# shield-v3.net
KiCad netlist of a schematic drawn in EAGLE
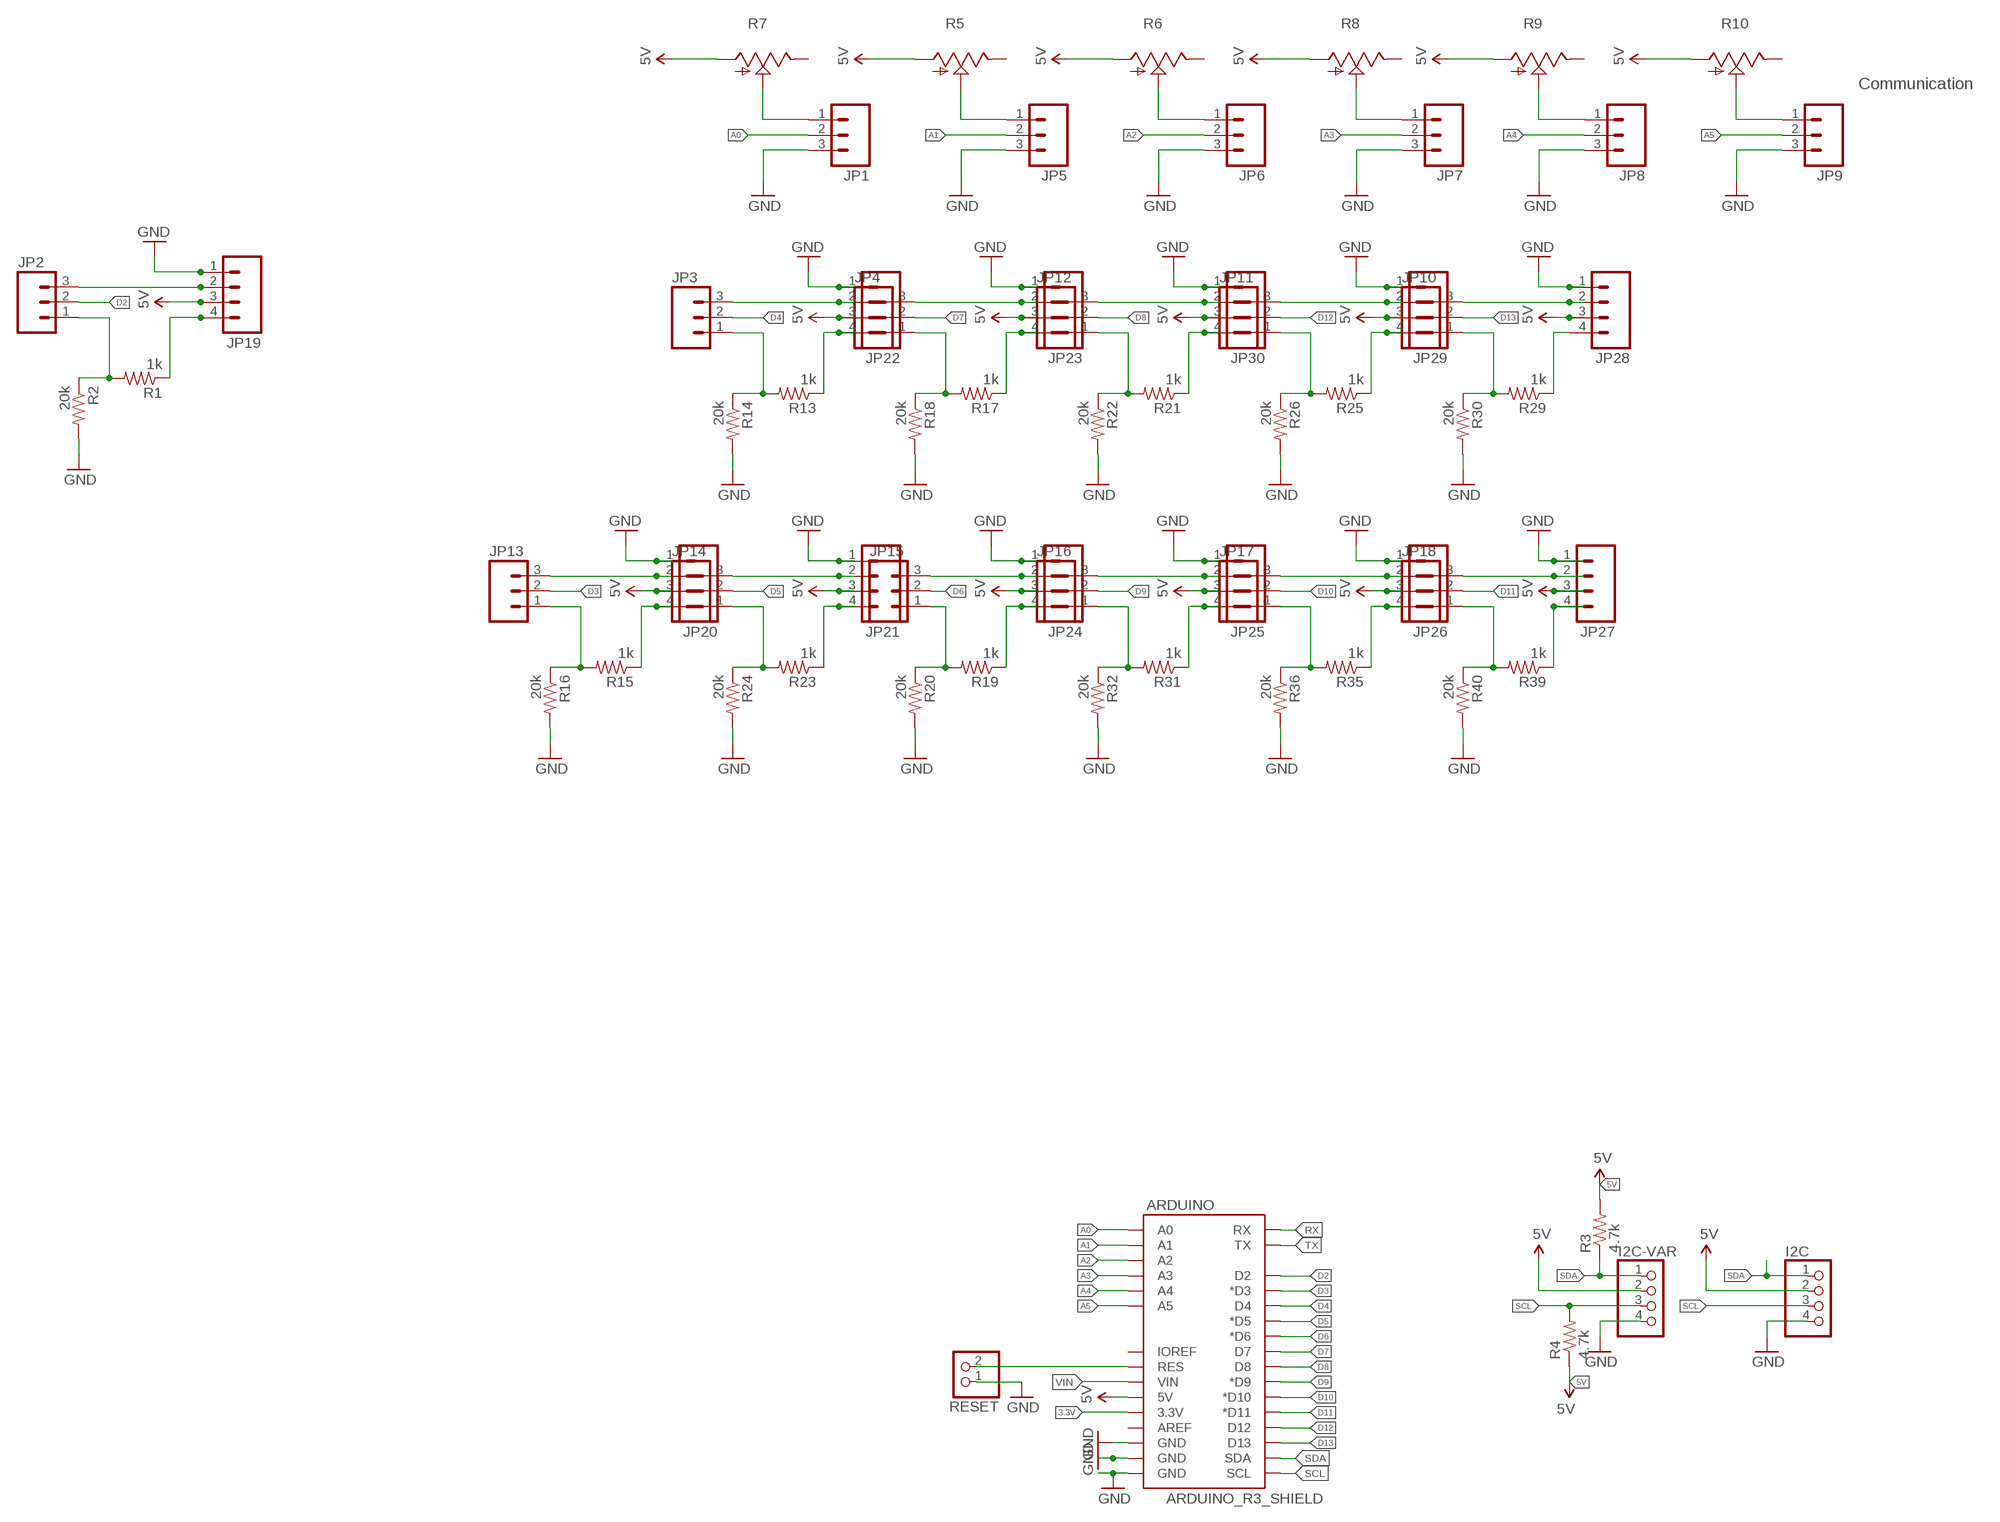
[diagram p0: schematic, sheet 1]

(export (version "E")
  (design (tool "Eeschema 10.0.6"))
  (components
    (comp (ref "ARDUINO")
      (value "ARDUINO_R3_SHIELD")
      (footprint "eagle-import:UNO_R3_SHIELD")
      (libsource (lib "eagle-import") (part "ARDUINO_R3_SHIELD"))
    )
    (comp (ref "I2C")
      (value "PINHD-1X4")
      (footprint "eagle-import:1X04")
      (libsource (lib "eagle-import") (part "PINHD-1X4"))
    )
    (comp (ref "I2C-VAR")
      (value "PINHD-1X4")
      (footprint "eagle-import:1X04")
      (libsource (lib "eagle-import") (part "PINHD-1X4"))
    )
    (comp (ref "JP1")
      (value "M03LOCK_NO_SILK")
      (footprint "eagle-import:1X03_LOCK_NO_SILK")
      (libsource (lib "eagle-import") (part "M03LOCK_NO_SILK"))
    )
    (comp (ref "JP2")
      (value "M03LOCK_NO_SILK")
      (footprint "eagle-import:1X03_LOCK_NO_SILK")
      (libsource (lib "eagle-import") (part "M03LOCK_NO_SILK"))
    )
    (comp (ref "JP3")
      (value "M03LOCK_NO_SILK")
      (footprint "eagle-import:1X03_LOCK_NO_SILK")
      (libsource (lib "eagle-import") (part "M03LOCK_NO_SILK"))
    )
    (comp (ref "JP4")
      (value "M03LOCK_NO_SILK")
      (footprint "eagle-import:1X03_LOCK_NO_SILK")
      (libsource (lib "eagle-import") (part "M03LOCK_NO_SILK"))
    )
    (comp (ref "JP5")
      (value "M03LOCK_NO_SILK")
      (footprint "eagle-import:1X03_LOCK_NO_SILK")
      (libsource (lib "eagle-import") (part "M03LOCK_NO_SILK"))
    )
    (comp (ref "JP6")
      (value "M03LOCK_NO_SILK")
      (footprint "eagle-import:1X03_LOCK_NO_SILK")
      (libsource (lib "eagle-import") (part "M03LOCK_NO_SILK"))
    )
    (comp (ref "JP7")
      (value "M03LOCK_NO_SILK")
      (footprint "eagle-import:1X03_LOCK_NO_SILK")
      (libsource (lib "eagle-import") (part "M03LOCK_NO_SILK"))
    )
    (comp (ref "JP8")
      (value "M03LOCK_NO_SILK")
      (footprint "eagle-import:1X03_LOCK_NO_SILK")
      (libsource (lib "eagle-import") (part "M03LOCK_NO_SILK"))
    )
    (comp (ref "JP9")
      (value "M03LOCK_NO_SILK")
      (footprint "eagle-import:1X03_LOCK_NO_SILK")
      (libsource (lib "eagle-import") (part "M03LOCK_NO_SILK"))
    )
    (comp (ref "JP10")
      (value "M03LOCK_NO_SILK")
      (footprint "eagle-import:1X03_LOCK_NO_SILK")
      (libsource (lib "eagle-import") (part "M03LOCK_NO_SILK"))
    )
    (comp (ref "JP11")
      (value "M03LOCK_NO_SILK")
      (footprint "eagle-import:1X03_LOCK_NO_SILK")
      (libsource (lib "eagle-import") (part "M03LOCK_NO_SILK"))
    )
    (comp (ref "JP12")
      (value "M03LOCK_NO_SILK")
      (footprint "eagle-import:1X03_LOCK_NO_SILK")
      (libsource (lib "eagle-import") (part "M03LOCK_NO_SILK"))
    )
    (comp (ref "JP13")
      (value "M03LOCK_NO_SILK")
      (footprint "eagle-import:1X03_LOCK_NO_SILK")
      (libsource (lib "eagle-import") (part "M03LOCK_NO_SILK"))
    )
    (comp (ref "JP14")
      (value "M03LOCK_NO_SILK")
      (footprint "eagle-import:1X03_LOCK_NO_SILK")
      (libsource (lib "eagle-import") (part "M03LOCK_NO_SILK"))
    )
    (comp (ref "JP15")
      (value "M03LOCK_NO_SILK")
      (footprint "eagle-import:1X03_LOCK_NO_SILK")
      (libsource (lib "eagle-import") (part "M03LOCK_NO_SILK"))
    )
    (comp (ref "JP16")
      (value "M03LOCK_NO_SILK")
      (footprint "eagle-import:1X03_LOCK_NO_SILK")
      (libsource (lib "eagle-import") (part "M03LOCK_NO_SILK"))
    )
    (comp (ref "JP17")
      (value "M03LOCK_NO_SILK")
      (footprint "eagle-import:1X03_LOCK_NO_SILK")
      (libsource (lib "eagle-import") (part "M03LOCK_NO_SILK"))
    )
    (comp (ref "JP18")
      (value "M03LOCK_NO_SILK")
      (footprint "eagle-import:1X03_LOCK_NO_SILK")
      (libsource (lib "eagle-import") (part "M03LOCK_NO_SILK"))
    )
    (comp (ref "JP19")
      (value "M04LOCK")
      (footprint "eagle-import:1X04_LOCK")
      (libsource (lib "eagle-import") (part "M04LOCK"))
    )
    (comp (ref "JP20")
      (value "M04LOCK")
      (footprint "eagle-import:1X04_LOCK")
      (libsource (lib "eagle-import") (part "M04LOCK"))
    )
    (comp (ref "JP21")
      (value "M04LOCK")
      (footprint "eagle-import:1X04_LOCK")
      (libsource (lib "eagle-import") (part "M04LOCK"))
    )
    (comp (ref "JP22")
      (value "M04LOCK")
      (footprint "eagle-import:1X04_LOCK")
      (libsource (lib "eagle-import") (part "M04LOCK"))
    )
    (comp (ref "JP23")
      (value "M04LOCK")
      (footprint "eagle-import:1X04_LOCK")
      (libsource (lib "eagle-import") (part "M04LOCK"))
    )
    (comp (ref "JP24")
      (value "M04LOCK")
      (footprint "eagle-import:1X04_LOCK")
      (libsource (lib "eagle-import") (part "M04LOCK"))
    )
    (comp (ref "JP25")
      (value "M04LOCK")
      (footprint "eagle-import:1X04_LOCK")
      (libsource (lib "eagle-import") (part "M04LOCK"))
    )
    (comp (ref "JP26")
      (value "M04LOCK")
      (footprint "eagle-import:1X04_LOCK")
      (libsource (lib "eagle-import") (part "M04LOCK"))
    )
    (comp (ref "JP27")
      (value "M04LOCK")
      (footprint "eagle-import:1X04_LOCK")
      (libsource (lib "eagle-import") (part "M04LOCK"))
    )
    (comp (ref "JP28")
      (value "M04LOCK")
      (footprint "eagle-import:1X04_LOCK")
      (libsource (lib "eagle-import") (part "M04LOCK"))
    )
    (comp (ref "JP29")
      (value "M04LOCK")
      (footprint "eagle-import:1X04_LOCK")
      (libsource (lib "eagle-import") (part "M04LOCK"))
    )
    (comp (ref "JP30")
      (value "M04LOCK")
      (footprint "eagle-import:1X04_LOCK")
      (libsource (lib "eagle-import") (part "M04LOCK"))
    )
    (comp (ref "R1")
      (value "1k")
      (footprint "eagle-import:AXIAL-0.3-KIT")
      (libsource (lib "eagle-import") (part "RESISTORKIT"))
    )
    (comp (ref "R2")
      (value "20k")
      (footprint "eagle-import:AXIAL-0.3-KIT")
      (libsource (lib "eagle-import") (part "RESISTORKIT"))
    )
    (comp (ref "R3")
      (value "4.7k")
      (footprint "eagle-import:AXIAL-0.3-KIT")
      (libsource (lib "eagle-import") (part "RESISTORKIT"))
    )
    (comp (ref "R4")
      (value "4.7k")
      (footprint "eagle-import:AXIAL-0.3-KIT")
      (libsource (lib "eagle-import") (part "RESISTORKIT"))
    )
    (comp (ref "R5")
      (value "TRIM_US-CA6V")
      (footprint "eagle-import:CA6V")
      (libsource (lib "eagle-import") (part "TRIM_US-CA6V"))
    )
    (comp (ref "R6")
      (value "TRIM_US-CA6V")
      (footprint "eagle-import:CA6V")
      (libsource (lib "eagle-import") (part "TRIM_US-CA6V"))
    )
    (comp (ref "R7")
      (value "TRIM_US-CA6V")
      (footprint "eagle-import:CA6V")
      (libsource (lib "eagle-import") (part "TRIM_US-CA6V"))
    )
    (comp (ref "R8")
      (value "TRIM_US-CA6V")
      (footprint "eagle-import:CA6V")
      (libsource (lib "eagle-import") (part "TRIM_US-CA6V"))
    )
    (comp (ref "R9")
      (value "TRIM_US-CA6V")
      (footprint "eagle-import:CA6V")
      (libsource (lib "eagle-import") (part "TRIM_US-CA6V"))
    )
    (comp (ref "R10")
      (value "TRIM_US-CA6V")
      (footprint "eagle-import:CA6V")
      (libsource (lib "eagle-import") (part "TRIM_US-CA6V"))
    )
    (comp (ref "R13")
      (value "1k")
      (footprint "eagle-import:AXIAL-0.3-KIT")
      (libsource (lib "eagle-import") (part "RESISTORKIT"))
    )
    (comp (ref "R14")
      (value "20k")
      (footprint "eagle-import:AXIAL-0.3-KIT")
      (libsource (lib "eagle-import") (part "RESISTORKIT"))
    )
    (comp (ref "R15")
      (value "1k")
      (footprint "eagle-import:AXIAL-0.3-KIT")
      (libsource (lib "eagle-import") (part "RESISTORKIT"))
    )
    (comp (ref "R16")
      (value "20k")
      (footprint "eagle-import:AXIAL-0.3-KIT")
      (libsource (lib "eagle-import") (part "RESISTORKIT"))
    )
    (comp (ref "R17")
      (value "1k")
      (footprint "eagle-import:AXIAL-0.3-KIT")
      (libsource (lib "eagle-import") (part "RESISTORKIT"))
    )
    (comp (ref "R18")
      (value "20k")
      (footprint "eagle-import:AXIAL-0.3-KIT")
      (libsource (lib "eagle-import") (part "RESISTORKIT"))
    )
    (comp (ref "R19")
      (value "1k")
      (footprint "eagle-import:AXIAL-0.3-KIT")
      (libsource (lib "eagle-import") (part "RESISTORKIT"))
    )
    (comp (ref "R20")
      (value "20k")
      (footprint "eagle-import:AXIAL-0.3-KIT")
      (libsource (lib "eagle-import") (part "RESISTORKIT"))
    )
    (comp (ref "R21")
      (value "1k")
      (footprint "eagle-import:AXIAL-0.3-KIT")
      (libsource (lib "eagle-import") (part "RESISTORKIT"))
    )
    (comp (ref "R22")
      (value "20k")
      (footprint "eagle-import:AXIAL-0.3-KIT")
      (libsource (lib "eagle-import") (part "RESISTORKIT"))
    )
    (comp (ref "R23")
      (value "1k")
      (footprint "eagle-import:AXIAL-0.3-KIT")
      (libsource (lib "eagle-import") (part "RESISTORKIT"))
    )
    (comp (ref "R24")
      (value "20k")
      (footprint "eagle-import:AXIAL-0.3-KIT")
      (libsource (lib "eagle-import") (part "RESISTORKIT"))
    )
    (comp (ref "R25")
      (value "1k")
      (footprint "eagle-import:AXIAL-0.3-KIT")
      (libsource (lib "eagle-import") (part "RESISTORKIT"))
    )
    (comp (ref "R26")
      (value "20k")
      (footprint "eagle-import:AXIAL-0.3-KIT")
      (libsource (lib "eagle-import") (part "RESISTORKIT"))
    )
    (comp (ref "R29")
      (value "1k")
      (footprint "eagle-import:AXIAL-0.3-KIT")
      (libsource (lib "eagle-import") (part "RESISTORKIT"))
    )
    (comp (ref "R30")
      (value "20k")
      (footprint "eagle-import:AXIAL-0.3-KIT")
      (libsource (lib "eagle-import") (part "RESISTORKIT"))
    )
    (comp (ref "R31")
      (value "1k")
      (footprint "eagle-import:AXIAL-0.3-KIT")
      (libsource (lib "eagle-import") (part "RESISTORKIT"))
    )
    (comp (ref "R32")
      (value "20k")
      (footprint "eagle-import:AXIAL-0.3-KIT")
      (libsource (lib "eagle-import") (part "RESISTORKIT"))
    )
    (comp (ref "R35")
      (value "1k")
      (footprint "eagle-import:AXIAL-0.3-KIT")
      (libsource (lib "eagle-import") (part "RESISTORKIT"))
    )
    (comp (ref "R36")
      (value "20k")
      (footprint "eagle-import:AXIAL-0.3-KIT")
      (libsource (lib "eagle-import") (part "RESISTORKIT"))
    )
    (comp (ref "R39")
      (value "1k")
      (footprint "eagle-import:AXIAL-0.3-KIT")
      (libsource (lib "eagle-import") (part "RESISTORKIT"))
    )
    (comp (ref "R40")
      (value "20k")
      (footprint "eagle-import:AXIAL-0.3-KIT")
      (libsource (lib "eagle-import") (part "RESISTORKIT"))
    )
    (comp (ref "RESET")
      (value "PINHD-1X2")
      (footprint "eagle-import:1X02")
      (libsource (lib "eagle-import") (part "PINHD-1X2"))
    )
  )
  (nets
    (net (code "1") (name "3.3V") (class "Default")
      (node (ref "ARDUINO") (pin "3.3V") (pinfunction "3.3V_3.3V") (pintype "bidirectional"))
    )
    (net (code "2") (name "5V") (class "Default")
      (node (ref "ARDUINO") (pin "5V") (pinfunction "5V_5V") (pintype "bidirectional"))
      (node (ref "I2C") (pin "2") (pinfunction "2_2") (pintype "passive"))
      (node (ref "I2C-VAR") (pin "2") (pinfunction "2_2") (pintype "passive"))
      (node (ref "JP19") (pin "3") (pinfunction "3_3") (pintype "passive"))
      (node (ref "JP20") (pin "3") (pinfunction "3_3") (pintype "passive"))
      (node (ref "JP21") (pin "3") (pinfunction "3_3") (pintype "passive"))
      (node (ref "JP22") (pin "3") (pinfunction "3_3") (pintype "passive"))
      (node (ref "JP23") (pin "3") (pinfunction "3_3") (pintype "passive"))
      (node (ref "JP24") (pin "3") (pinfunction "3_3") (pintype "passive"))
      (node (ref "JP25") (pin "3") (pinfunction "3_3") (pintype "passive"))
      (node (ref "JP26") (pin "3") (pinfunction "3_3") (pintype "passive"))
      (node (ref "JP27") (pin "3") (pinfunction "3_3") (pintype "passive"))
      (node (ref "JP28") (pin "3") (pinfunction "3_3") (pintype "passive"))
      (node (ref "JP29") (pin "3") (pinfunction "3_3") (pintype "passive"))
      (node (ref "JP30") (pin "3") (pinfunction "3_3") (pintype "passive"))
      (node (ref "R10") (pin "A") (pinfunction "A_A") (pintype "passive"))
      (node (ref "R3") (pin "P$2") (pinfunction "2_P$2") (pintype "passive"))
      (node (ref "R4") (pin "P$1") (pinfunction "1_P$1") (pintype "passive"))
      (node (ref "R5") (pin "A") (pinfunction "A_A") (pintype "passive"))
      (node (ref "R6") (pin "A") (pinfunction "A_A") (pintype "passive"))
      (node (ref "R7") (pin "A") (pinfunction "A_A") (pintype "passive"))
      (node (ref "R8") (pin "A") (pinfunction "A_A") (pintype "passive"))
      (node (ref "R9") (pin "A") (pinfunction "A_A") (pintype "passive"))
    )
    (net (code "3") (name "A0") (class "Default")
      (node (ref "ARDUINO") (pin "A0") (pinfunction "A0_A0") (pintype "bidirectional"))
      (node (ref "JP1") (pin "2") (pinfunction "2_2") (pintype "passive"))
    )
    (net (code "4") (name "A1") (class "Default")
      (node (ref "ARDUINO") (pin "A1") (pinfunction "A1_A1") (pintype "bidirectional"))
      (node (ref "JP5") (pin "2") (pinfunction "2_2") (pintype "passive"))
    )
    (net (code "5") (name "A2") (class "Default")
      (node (ref "ARDUINO") (pin "A2") (pinfunction "A2_A2") (pintype "bidirectional"))
      (node (ref "JP6") (pin "2") (pinfunction "2_2") (pintype "passive"))
    )
    (net (code "6") (name "A3") (class "Default")
      (node (ref "ARDUINO") (pin "A3") (pinfunction "A3_A3") (pintype "bidirectional"))
      (node (ref "JP7") (pin "2") (pinfunction "2_2") (pintype "passive"))
    )
    (net (code "7") (name "A4") (class "Default")
      (node (ref "ARDUINO") (pin "A4") (pinfunction "A4_A4") (pintype "bidirectional"))
      (node (ref "JP8") (pin "2") (pinfunction "2_2") (pintype "passive"))
    )
    (net (code "8") (name "A5") (class "Default")
      (node (ref "ARDUINO") (pin "A5") (pinfunction "A5_A5") (pintype "bidirectional"))
      (node (ref "JP9") (pin "2") (pinfunction "2_2") (pintype "passive"))
    )
    (net (code "9") (name "D2") (class "Default")
      (node (ref "ARDUINO") (pin "D2") (pinfunction "D2_D2") (pintype "bidirectional"))
      (node (ref "JP2") (pin "2") (pinfunction "2_2") (pintype "passive"))
    )
    (net (code "10") (name "D3") (class "Default")
      (node (ref "ARDUINO") (pin "D3") (pinfunction "*D3_D3") (pintype "bidirectional"))
      (node (ref "JP13") (pin "2") (pinfunction "2_2") (pintype "passive"))
    )
    (net (code "11") (name "D4") (class "Default")
      (node (ref "ARDUINO") (pin "D4") (pinfunction "D4_D4") (pintype "bidirectional"))
      (node (ref "JP3") (pin "2") (pinfunction "2_2") (pintype "passive"))
    )
    (net (code "12") (name "D5") (class "Default")
      (node (ref "ARDUINO") (pin "D5") (pinfunction "*D5_D5") (pintype "bidirectional"))
      (node (ref "JP14") (pin "2") (pinfunction "2_2") (pintype "passive"))
    )
    (net (code "13") (name "D6") (class "Default")
      (node (ref "ARDUINO") (pin "D6") (pinfunction "*D6_D6") (pintype "bidirectional"))
      (node (ref "JP15") (pin "2") (pinfunction "2_2") (pintype "passive"))
    )
    (net (code "14") (name "D7") (class "Default")
      (node (ref "ARDUINO") (pin "D7") (pinfunction "D7_D7") (pintype "bidirectional"))
      (node (ref "JP4") (pin "2") (pinfunction "2_2") (pintype "passive"))
    )
    (net (code "15") (name "D8") (class "Default")
      (node (ref "ARDUINO") (pin "D8") (pinfunction "D8_D8") (pintype "bidirectional"))
      (node (ref "JP12") (pin "2") (pinfunction "2_2") (pintype "passive"))
    )
    (net (code "16") (name "D9") (class "Default")
      (node (ref "ARDUINO") (pin "D9") (pinfunction "*D9_D9") (pintype "bidirectional"))
      (node (ref "JP16") (pin "2") (pinfunction "2_2") (pintype "passive"))
    )
    (net (code "17") (name "D10") (class "Default")
      (node (ref "ARDUINO") (pin "D10") (pinfunction "*D10_D10") (pintype "bidirectional"))
      (node (ref "JP17") (pin "2") (pinfunction "2_2") (pintype "passive"))
    )
    (net (code "18") (name "D11") (class "Default")
      (node (ref "ARDUINO") (pin "D11") (pinfunction "*D11_D11") (pintype "bidirectional"))
      (node (ref "JP18") (pin "2") (pinfunction "2_2") (pintype "passive"))
    )
    (net (code "19") (name "D12") (class "Default")
      (node (ref "ARDUINO") (pin "D12") (pinfunction "D12_D12") (pintype "bidirectional"))
      (node (ref "JP11") (pin "2") (pinfunction "2_2") (pintype "passive"))
    )
    (net (code "20") (name "D13") (class "Default")
      (node (ref "ARDUINO") (pin "D13") (pinfunction "D13_D13") (pintype "bidirectional"))
      (node (ref "JP10") (pin "2") (pinfunction "2_2") (pintype "passive"))
    )
    (net (code "21") (name "GND") (class "Default")
      (node (ref "ARDUINO") (pin "GND@0") (pinfunction "GND_GND@0") (pintype "bidirectional"))
      (node (ref "ARDUINO") (pin "GND@1") (pinfunction "GND_GND@1") (pintype "bidirectional"))
      (node (ref "ARDUINO") (pin "GND@2") (pinfunction "GND_GND@2") (pintype "bidirectional"))
      (node (ref "I2C") (pin "4") (pinfunction "4_4") (pintype "passive"))
      (node (ref "I2C-VAR") (pin "4") (pinfunction "4_4") (pintype "passive"))
      (node (ref "JP1") (pin "3") (pinfunction "3_3") (pintype "passive"))
      (node (ref "JP19") (pin "1") (pinfunction "1_1") (pintype "passive"))
      (node (ref "JP20") (pin "1") (pinfunction "1_1") (pintype "passive"))
      (node (ref "JP21") (pin "1") (pinfunction "1_1") (pintype "passive"))
      (node (ref "JP22") (pin "1") (pinfunction "1_1") (pintype "passive"))
      (node (ref "JP23") (pin "1") (pinfunction "1_1") (pintype "passive"))
      (node (ref "JP24") (pin "1") (pinfunction "1_1") (pintype "passive"))
      (node (ref "JP25") (pin "1") (pinfunction "1_1") (pintype "passive"))
      (node (ref "JP26") (pin "1") (pinfunction "1_1") (pintype "passive"))
      (node (ref "JP27") (pin "1") (pinfunction "1_1") (pintype "passive"))
      (node (ref "JP28") (pin "1") (pinfunction "1_1") (pintype "passive"))
      (node (ref "JP29") (pin "1") (pinfunction "1_1") (pintype "passive"))
      (node (ref "JP30") (pin "1") (pinfunction "1_1") (pintype "passive"))
      (node (ref "JP5") (pin "3") (pinfunction "3_3") (pintype "passive"))
      (node (ref "JP6") (pin "3") (pinfunction "3_3") (pintype "passive"))
      (node (ref "JP7") (pin "3") (pinfunction "3_3") (pintype "passive"))
      (node (ref "JP8") (pin "3") (pinfunction "3_3") (pintype "passive"))
      (node (ref "JP9") (pin "3") (pinfunction "3_3") (pintype "passive"))
      (node (ref "R14") (pin "P$2") (pinfunction "2_P$2") (pintype "passive"))
      (node (ref "R16") (pin "P$2") (pinfunction "2_P$2") (pintype "passive"))
      (node (ref "R18") (pin "P$2") (pinfunction "2_P$2") (pintype "passive"))
      (node (ref "R2") (pin "P$2") (pinfunction "2_P$2") (pintype "passive"))
      (node (ref "R20") (pin "P$2") (pinfunction "2_P$2") (pintype "passive"))
      (node (ref "R22") (pin "P$2") (pinfunction "2_P$2") (pintype "passive"))
      (node (ref "R24") (pin "P$2") (pinfunction "2_P$2") (pintype "passive"))
      (node (ref "R26") (pin "P$2") (pinfunction "2_P$2") (pintype "passive"))
      (node (ref "R30") (pin "P$2") (pinfunction "2_P$2") (pintype "passive"))
      (node (ref "R32") (pin "P$2") (pinfunction "2_P$2") (pintype "passive"))
      (node (ref "R36") (pin "P$2") (pinfunction "2_P$2") (pintype "passive"))
      (node (ref "R40") (pin "P$2") (pinfunction "2_P$2") (pintype "passive"))
      (node (ref "RESET") (pin "1") (pinfunction "1_1") (pintype "passive"))
    )
    (net (code "22") (name "Net-(ARDUINO-PadRES)") (class "Default")
      (node (ref "ARDUINO") (pin "RES") (pinfunction "RES_RES") (pintype "bidirectional"))
      (node (ref "RESET") (pin "2") (pinfunction "2_2") (pintype "passive"))
    )
    (net (code "23") (name "Net-(JP1-Pad1)") (class "Default")
      (node (ref "JP1") (pin "1") (pinfunction "1_1") (pintype "passive"))
      (node (ref "R7") (pin "S") (pinfunction "S_S") (pintype "passive"))
    )
    (net (code "24") (name "Net-(JP5-Pad1)") (class "Default")
      (node (ref "JP5") (pin "1") (pinfunction "1_1") (pintype "passive"))
      (node (ref "R5") (pin "S") (pinfunction "S_S") (pintype "passive"))
    )
    (net (code "25") (name "Net-(JP6-Pad1)") (class "Default")
      (node (ref "JP6") (pin "1") (pinfunction "1_1") (pintype "passive"))
      (node (ref "R6") (pin "S") (pinfunction "S_S") (pintype "passive"))
    )
    (net (code "26") (name "Net-(JP7-Pad1)") (class "Default")
      (node (ref "JP7") (pin "1") (pinfunction "1_1") (pintype "passive"))
      (node (ref "R8") (pin "S") (pinfunction "S_S") (pintype "passive"))
    )
    (net (code "27") (name "Net-(JP8-Pad1)") (class "Default")
      (node (ref "JP8") (pin "1") (pinfunction "1_1") (pintype "passive"))
      (node (ref "R9") (pin "S") (pinfunction "S_S") (pintype "passive"))
    )
    (net (code "28") (name "Net-(JP9-Pad1)") (class "Default")
      (node (ref "JP9") (pin "1") (pinfunction "1_1") (pintype "passive"))
      (node (ref "R10") (pin "S") (pinfunction "S_S") (pintype "passive"))
    )
    (net (code "29") (name "Net-(JP10-Pad3)") (class "Default")
      (node (ref "JP10") (pin "3") (pinfunction "3_3") (pintype "passive"))
      (node (ref "JP28") (pin "2") (pinfunction "2_2") (pintype "passive"))
    )
    (net (code "30") (name "Net-(JP11-Pad3)") (class "Default")
      (node (ref "JP11") (pin "3") (pinfunction "3_3") (pintype "passive"))
      (node (ref "JP29") (pin "2") (pinfunction "2_2") (pintype "passive"))
    )
    (net (code "31") (name "Net-(JP12-Pad3)") (class "Default")
      (node (ref "JP12") (pin "3") (pinfunction "3_3") (pintype "passive"))
      (node (ref "JP30") (pin "2") (pinfunction "2_2") (pintype "passive"))
    )
    (net (code "32") (name "Net-(JP13-Pad3)") (class "Default")
      (node (ref "JP13") (pin "3") (pinfunction "3_3") (pintype "passive"))
      (node (ref "JP20") (pin "2") (pinfunction "2_2") (pintype "passive"))
    )
    (net (code "33") (name "Net-(JP14-Pad3)") (class "Default")
      (node (ref "JP14") (pin "3") (pinfunction "3_3") (pintype "passive"))
      (node (ref "JP21") (pin "2") (pinfunction "2_2") (pintype "passive"))
    )
    (net (code "34") (name "Net-(JP15-Pad3)") (class "Default")
      (node (ref "JP15") (pin "3") (pinfunction "3_3") (pintype "passive"))
      (node (ref "JP24") (pin "2") (pinfunction "2_2") (pintype "passive"))
    )
    (net (code "35") (name "Net-(JP16-Pad3)") (class "Default")
      (node (ref "JP16") (pin "3") (pinfunction "3_3") (pintype "passive"))
      (node (ref "JP25") (pin "2") (pinfunction "2_2") (pintype "passive"))
    )
    (net (code "36") (name "Net-(JP17-Pad3)") (class "Default")
      (node (ref "JP17") (pin "3") (pinfunction "3_3") (pintype "passive"))
      (node (ref "JP26") (pin "2") (pinfunction "2_2") (pintype "passive"))
    )
    (net (code "37") (name "Net-(JP18-Pad3)") (class "Default")
      (node (ref "JP18") (pin "3") (pinfunction "3_3") (pintype "passive"))
      (node (ref "JP27") (pin "2") (pinfunction "2_2") (pintype "passive"))
    )
    (net (code "38") (name "Net-(JP19-Pad2)") (class "Default")
      (node (ref "JP19") (pin "2") (pinfunction "2_2") (pintype "passive"))
      (node (ref "JP2") (pin "3") (pinfunction "3_3") (pintype "passive"))
    )
    (net (code "39") (name "Net-(JP22-Pad2)") (class "Default")
      (node (ref "JP22") (pin "2") (pinfunction "2_2") (pintype "passive"))
      (node (ref "JP3") (pin "3") (pinfunction "3_3") (pintype "passive"))
    )
    (net (code "40") (name "Net-(JP23-Pad2)") (class "Default")
      (node (ref "JP23") (pin "2") (pinfunction "2_2") (pintype "passive"))
      (node (ref "JP4") (pin "3") (pinfunction "3_3") (pintype "passive"))
    )
    (net (code "41") (name "Net-(R1-1)") (class "Default")
      (node (ref "JP19") (pin "4") (pinfunction "4_4") (pintype "passive"))
      (node (ref "R1") (pin "P$1") (pinfunction "1_P$1") (pintype "passive"))
    )
    (net (code "42") (name "Net-(R1-2)") (class "Default")
      (node (ref "JP2") (pin "1") (pinfunction "1_1") (pintype "passive"))
      (node (ref "R1") (pin "P$2") (pinfunction "2_P$2") (pintype "passive"))
      (node (ref "R2") (pin "P$1") (pinfunction "1_P$1") (pintype "passive"))
    )
    (net (code "43") (name "Net-(R13-1)") (class "Default")
      (node (ref "JP22") (pin "4") (pinfunction "4_4") (pintype "passive"))
      (node (ref "R13") (pin "P$1") (pinfunction "1_P$1") (pintype "passive"))
    )
    (net (code "44") (name "Net-(R13-2)") (class "Default")
      (node (ref "JP3") (pin "1") (pinfunction "1_1") (pintype "passive"))
      (node (ref "R13") (pin "P$2") (pinfunction "2_P$2") (pintype "passive"))
      (node (ref "R14") (pin "P$1") (pinfunction "1_P$1") (pintype "passive"))
    )
    (net (code "45") (name "Net-(R15-1)") (class "Default")
      (node (ref "JP20") (pin "4") (pinfunction "4_4") (pintype "passive"))
      (node (ref "R15") (pin "P$1") (pinfunction "1_P$1") (pintype "passive"))
    )
    (net (code "46") (name "Net-(R15-2)") (class "Default")
      (node (ref "JP13") (pin "1") (pinfunction "1_1") (pintype "passive"))
      (node (ref "R15") (pin "P$2") (pinfunction "2_P$2") (pintype "passive"))
      (node (ref "R16") (pin "P$1") (pinfunction "1_P$1") (pintype "passive"))
    )
    (net (code "47") (name "Net-(R17-1)") (class "Default")
      (node (ref "JP23") (pin "4") (pinfunction "4_4") (pintype "passive"))
      (node (ref "R17") (pin "P$1") (pinfunction "1_P$1") (pintype "passive"))
    )
    (net (code "48") (name "Net-(R17-2)") (class "Default")
      (node (ref "JP4") (pin "1") (pinfunction "1_1") (pintype "passive"))
      (node (ref "R17") (pin "P$2") (pinfunction "2_P$2") (pintype "passive"))
      (node (ref "R18") (pin "P$1") (pinfunction "1_P$1") (pintype "passive"))
    )
    (net (code "49") (name "Net-(R19-1)") (class "Default")
      (node (ref "JP24") (pin "4") (pinfunction "4_4") (pintype "passive"))
      (node (ref "R19") (pin "P$1") (pinfunction "1_P$1") (pintype "passive"))
    )
    (net (code "50") (name "Net-(R19-2)") (class "Default")
      (node (ref "JP15") (pin "1") (pinfunction "1_1") (pintype "passive"))
      (node (ref "R19") (pin "P$2") (pinfunction "2_P$2") (pintype "passive"))
      (node (ref "R20") (pin "P$1") (pinfunction "1_P$1") (pintype "passive"))
    )
    (net (code "51") (name "Net-(R21-1)") (class "Default")
      (node (ref "JP30") (pin "4") (pinfunction "4_4") (pintype "passive"))
      (node (ref "R21") (pin "P$1") (pinfunction "1_P$1") (pintype "passive"))
    )
    (net (code "52") (name "Net-(R21-2)") (class "Default")
      (node (ref "JP12") (pin "1") (pinfunction "1_1") (pintype "passive"))
      (node (ref "R21") (pin "P$2") (pinfunction "2_P$2") (pintype "passive"))
      (node (ref "R22") (pin "P$1") (pinfunction "1_P$1") (pintype "passive"))
    )
    (net (code "53") (name "Net-(R23-1)") (class "Default")
      (node (ref "JP21") (pin "4") (pinfunction "4_4") (pintype "passive"))
      (node (ref "R23") (pin "P$1") (pinfunction "1_P$1") (pintype "passive"))
    )
    (net (code "54") (name "Net-(R23-2)") (class "Default")
      (node (ref "JP14") (pin "1") (pinfunction "1_1") (pintype "passive"))
      (node (ref "R23") (pin "P$2") (pinfunction "2_P$2") (pintype "passive"))
      (node (ref "R24") (pin "P$1") (pinfunction "1_P$1") (pintype "passive"))
    )
    (net (code "55") (name "Net-(R25-1)") (class "Default")
      (node (ref "JP29") (pin "4") (pinfunction "4_4") (pintype "passive"))
      (node (ref "R25") (pin "P$1") (pinfunction "1_P$1") (pintype "passive"))
    )
    (net (code "56") (name "Net-(R25-2)") (class "Default")
      (node (ref "JP11") (pin "1") (pinfunction "1_1") (pintype "passive"))
      (node (ref "R25") (pin "P$2") (pinfunction "2_P$2") (pintype "passive"))
      (node (ref "R26") (pin "P$1") (pinfunction "1_P$1") (pintype "passive"))
    )
    (net (code "57") (name "Net-(R29-1)") (class "Default")
      (node (ref "JP28") (pin "4") (pinfunction "4_4") (pintype "passive"))
      (node (ref "R29") (pin "P$1") (pinfunction "1_P$1") (pintype "passive"))
    )
    (net (code "58") (name "Net-(R29-2)") (class "Default")
      (node (ref "JP10") (pin "1") (pinfunction "1_1") (pintype "passive"))
      (node (ref "R29") (pin "P$2") (pinfunction "2_P$2") (pintype "passive"))
      (node (ref "R30") (pin "P$1") (pinfunction "1_P$1") (pintype "passive"))
    )
    (net (code "59") (name "Net-(R31-1)") (class "Default")
      (node (ref "JP25") (pin "4") (pinfunction "4_4") (pintype "passive"))
      (node (ref "R31") (pin "P$1") (pinfunction "1_P$1") (pintype "passive"))
    )
    (net (code "60") (name "Net-(R31-2)") (class "Default")
      (node (ref "JP16") (pin "1") (pinfunction "1_1") (pintype "passive"))
      (node (ref "R31") (pin "P$2") (pinfunction "2_P$2") (pintype "passive"))
      (node (ref "R32") (pin "P$1") (pinfunction "1_P$1") (pintype "passive"))
    )
    (net (code "61") (name "Net-(R35-1)") (class "Default")
      (node (ref "JP26") (pin "4") (pinfunction "4_4") (pintype "passive"))
      (node (ref "R35") (pin "P$1") (pinfunction "1_P$1") (pintype "passive"))
    )
    (net (code "62") (name "Net-(R35-2)") (class "Default")
      (node (ref "JP17") (pin "1") (pinfunction "1_1") (pintype "passive"))
      (node (ref "R35") (pin "P$2") (pinfunction "2_P$2") (pintype "passive"))
      (node (ref "R36") (pin "P$1") (pinfunction "1_P$1") (pintype "passive"))
    )
    (net (code "63") (name "Net-(R39-1)") (class "Default")
      (node (ref "JP27") (pin "4") (pinfunction "4_4") (pintype "passive"))
      (node (ref "R39") (pin "P$1") (pinfunction "1_P$1") (pintype "passive"))
    )
    (net (code "64") (name "Net-(R39-2)") (class "Default")
      (node (ref "JP18") (pin "1") (pinfunction "1_1") (pintype "passive"))
      (node (ref "R39") (pin "P$2") (pinfunction "2_P$2") (pintype "passive"))
      (node (ref "R40") (pin "P$1") (pinfunction "1_P$1") (pintype "passive"))
    )
    (net (code "65") (name "RX") (class "Default")
      (node (ref "ARDUINO") (pin "RX") (pinfunction "RX_RX") (pintype "bidirectional"))
    )
    (net (code "66") (name "SCL") (class "Default")
      (node (ref "ARDUINO") (pin "SCL") (pinfunction "SCL_SCL") (pintype "bidirectional"))
      (node (ref "I2C") (pin "3") (pinfunction "3_3") (pintype "passive"))
      (node (ref "I2C-VAR") (pin "3") (pinfunction "3_3") (pintype "passive"))
      (node (ref "R4") (pin "P$2") (pinfunction "2_P$2") (pintype "passive"))
    )
    (net (code "67") (name "SDA") (class "Default")
      (node (ref "ARDUINO") (pin "SDA") (pinfunction "SDA_SDA") (pintype "bidirectional"))
      (node (ref "I2C") (pin "1") (pinfunction "1_1") (pintype "passive"))
      (node (ref "I2C-VAR") (pin "1") (pinfunction "1_1") (pintype "passive"))
      (node (ref "R3") (pin "P$1") (pinfunction "1_P$1") (pintype "passive"))
    )
    (net (code "68") (name "TX") (class "Default")
      (node (ref "ARDUINO") (pin "TX") (pinfunction "TX_TX") (pintype "bidirectional"))
    )
    (net (code "69") (name "VIN") (class "Default")
      (node (ref "ARDUINO") (pin "VIN") (pinfunction "VIN_VIN") (pintype "bidirectional"))
    )
    (net (code "70") (name "unconnected-(ARDUINO-PadAREF)") (class "Default")
      (node (ref "ARDUINO") (pin "AREF") (pinfunction "AREF_AREF") (pintype "bidirectional"))
    )
    (net (code "71") (name "unconnected-(ARDUINO-PadIOREF)") (class "Default")
      (node (ref "ARDUINO") (pin "IOREF") (pinfunction "IOREF_IOREF") (pintype "bidirectional"))
    )
    (net (code "72") (name "unconnected-(R5-PadE)") (class "Default")
      (node (ref "R5") (pin "E") (pinfunction "E_E") (pintype "passive"))
    )
    (net (code "73") (name "unconnected-(R6-PadE)") (class "Default")
      (node (ref "R6") (pin "E") (pinfunction "E_E") (pintype "passive"))
    )
    (net (code "74") (name "unconnected-(R7-PadE)") (class "Default")
      (node (ref "R7") (pin "E") (pinfunction "E_E") (pintype "passive"))
    )
    (net (code "75") (name "unconnected-(R8-PadE)") (class "Default")
      (node (ref "R8") (pin "E") (pinfunction "E_E") (pintype "passive"))
    )
    (net (code "76") (name "unconnected-(R9-PadE)") (class "Default")
      (node (ref "R9") (pin "E") (pinfunction "E_E") (pintype "passive"))
    )
    (net (code "77") (name "unconnected-(R10-PadE)") (class "Default")
      (node (ref "R10") (pin "E") (pinfunction "E_E") (pintype "passive"))
    )
  )
)
